# IMU.net
KiCad netlist of a schematic drawn in Altium Designer
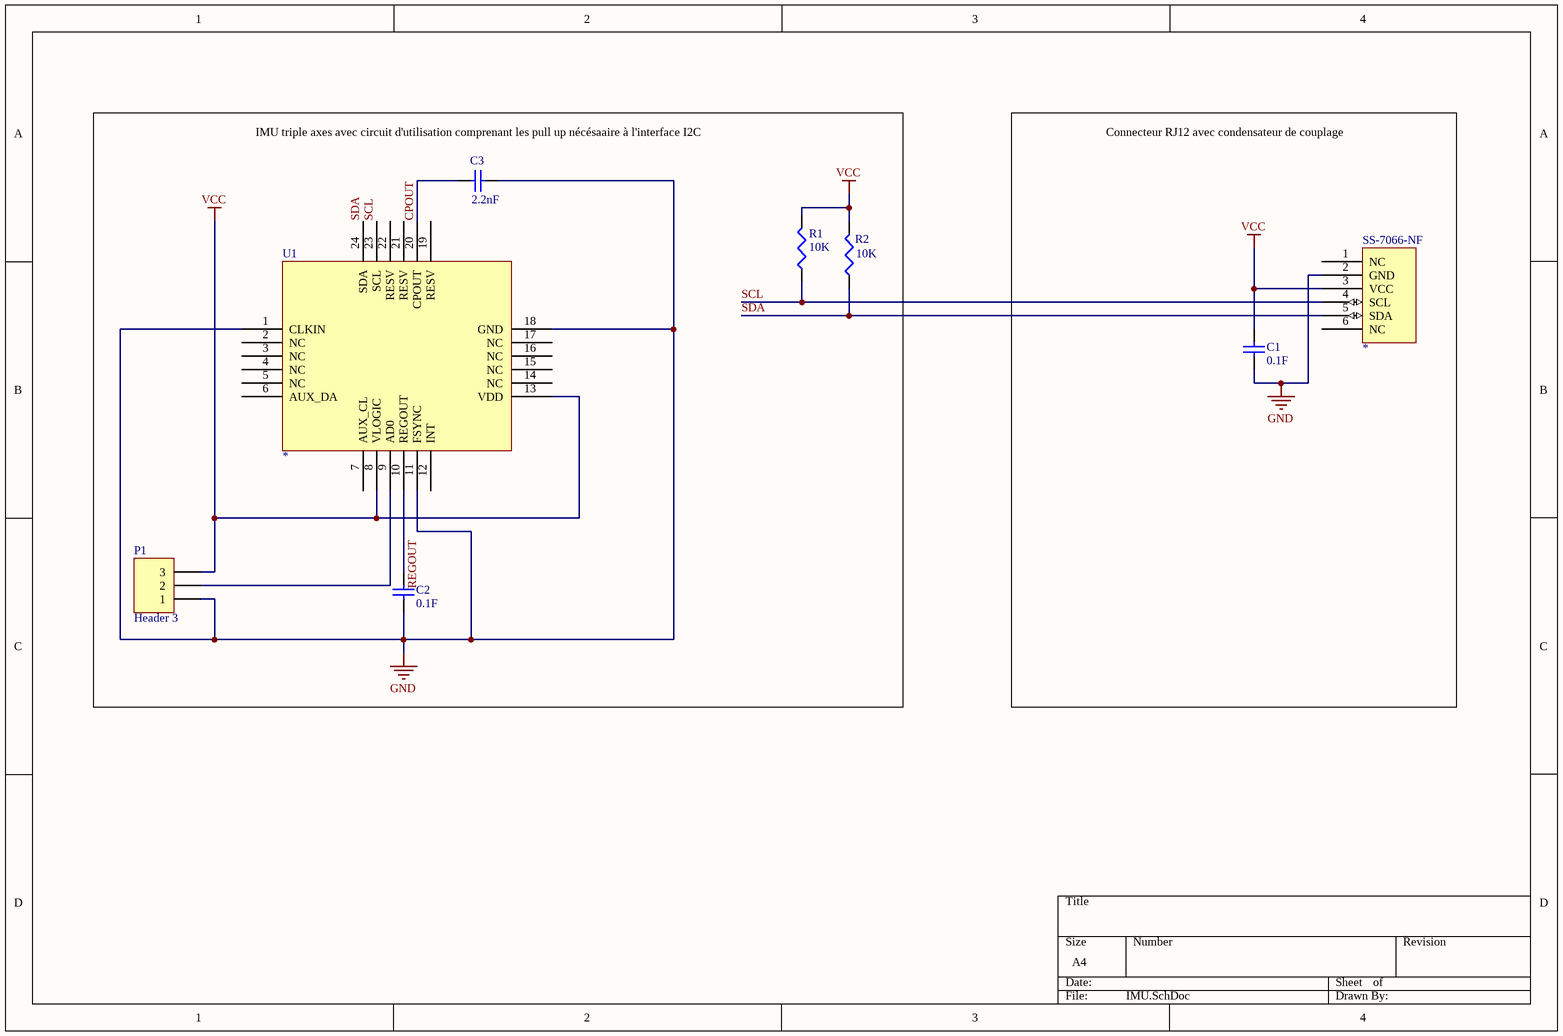
[diagram p0: IMU.SchDoc]

(export (version "E")
  (design (tool "Eeschema 10.0.6"))
  (components
    (comp (ref "C1")
      (value "0.1F")
      (footprint "C0805")
      (description "Capacitor 0.1uF")
      (fields (field (name "Comment") "Cap 0.1uF") (field (name "PUBLISHER") "Altium Limited"))
      (libsource (lib "MOvIT-Detect PCB") (part "Cap 0.1uF"))
    )
    (comp (ref "C2")
      (value "0.1F")
      (footprint "C0805")
      (description "Capacitor 0.1uF")
      (fields (field (name "Comment") "Cap 0.1uF") (field (name "PUBLISHER") "Altium Limited"))
      (libsource (lib "MOvIT-Detect PCB") (part "Cap 0.1uF"))
    )
    (comp (ref "C3")
      (value "2.2nF")
      (footprint "C0805")
      (description "Capacitor 2.2nF")
      (fields (field (name "Comment") "Cap 2.2nF") (field (name "PUBLISHER") "Altium Limited"))
      (libsource (lib "MOvIT-Detect PCB") (part "Cap 2.2nF"))
    )
    (comp (ref "P1")
      (value "Header 3")
      (footprint "HDR1X3")
      (description "Header, 3-Pin")
      (fields (field (name "PUBLISHER") "Altium Limited"))
      (libsource (lib "MOvIT-Detect PCB") (part "Header 3"))
    )
    (comp (ref "R1")
      (value "10K")
      (footprint "6-0805_N")
      (description "Resistor 10K")
      (fields (field (name "Comment") "Res 10K") (field (name "PUBLISHER") "Altium Limited"))
      (libsource (lib "MOvIT-Detect PCB") (part "Res 10K"))
    )
    (comp (ref "R2")
      (value "10K")
      (footprint "6-0805_N")
      (description "Resistor 10K")
      (fields (field (name "Comment") "Res 10K") (field (name "PUBLISHER") "Altium Limited"))
      (libsource (lib "MOvIT-Detect PCB") (part "Res 10K"))
    )
    (comp (ref "SS-7066-NF")
      (value "*")
      (footprint "SS-7066-NF")
      (description "RJ12 Connector")
      (libsource (lib "MOvIT-Detect PCB") (part "SS-7066-NF"))
    )
    (comp (ref "U1")
      (value "*")
      (footprint "MPU6050")
      (description "3 Axis IMU")
      (libsource (lib "MOvIT-Detect PCB") (part "MPU6050"))
    )
  )
  (nets
    (net (code "1") (name "/CPOUT") (class "Default")
      (node (ref "C3") (pin "1") (pinfunction "1_1") (pintype "passive"))
      (node (ref "U1") (pin "20") (pinfunction "CPOUT_20") (pintype "passive"))
    )
    (net (code "2") (name "/REGOUT") (class "Default")
      (node (ref "C2") (pin "2") (pinfunction "2_2") (pintype "passive"))
      (node (ref "U1") (pin "10") (pinfunction "REGOUT_10") (pintype "passive"))
    )
    (net (code "3") (name "/SCL") (class "Default")
      (node (ref "R1") (pin "1") (pinfunction "1_1") (pintype "passive"))
      (node (ref "SS-7066-NF") (pin "4") (pinfunction "SCL_4") (pintype "bidirectional"))
      (node (ref "U1") (pin "23") (pinfunction "SCL_23") (pintype "passive"))
    )
    (net (code "4") (name "/SDA") (class "Default")
      (node (ref "R2") (pin "1") (pinfunction "1_1") (pintype "passive"))
      (node (ref "SS-7066-NF") (pin "5") (pinfunction "SDA_5") (pintype "bidirectional"))
      (node (ref "U1") (pin "24") (pinfunction "SDA_24") (pintype "passive"))
    )
    (net (code "5") (name "GND") (class "Default")
      (node (ref "C1") (pin "1") (pinfunction "1_1") (pintype "passive"))
      (node (ref "C2") (pin "1") (pinfunction "1_1") (pintype "passive"))
      (node (ref "C3") (pin "2") (pinfunction "2_2") (pintype "passive"))
      (node (ref "P1") (pin "1") (pinfunction "1_1") (pintype "passive"))
      (node (ref "SS-7066-NF") (pin "2") (pinfunction "GND_2") (pintype "passive"))
      (node (ref "U1") (pin "1") (pinfunction "CLKIN_1") (pintype "passive"))
      (node (ref "U1") (pin "11") (pinfunction "FSYNC_11") (pintype "passive"))
      (node (ref "U1") (pin "18") (pinfunction "GND_18") (pintype "passive"))
    )
    (net (code "6") (name "Net-(U1-AD0)") (class "Default")
      (node (ref "P1") (pin "2") (pinfunction "2_2") (pintype "passive"))
      (node (ref "U1") (pin "9") (pinfunction "AD0_9") (pintype "passive"))
    )
    (net (code "7") (name "VCC") (class "Default")
      (node (ref "C1") (pin "2") (pinfunction "2_2") (pintype "passive"))
      (node (ref "P1") (pin "3") (pinfunction "3_3") (pintype "passive"))
      (node (ref "R1") (pin "2") (pinfunction "2_2") (pintype "passive"))
      (node (ref "R2") (pin "2") (pinfunction "2_2") (pintype "passive"))
      (node (ref "SS-7066-NF") (pin "3") (pinfunction "VCC_3") (pintype "passive"))
      (node (ref "U1") (pin "13") (pinfunction "VDD_13") (pintype "passive"))
      (node (ref "U1") (pin "8") (pinfunction "VLOGIC_8") (pintype "passive"))
    )
    (net (code "8") (name "unconnected-(SS-7066-NF-NC-Pad1)") (class "Default")
      (node (ref "SS-7066-NF") (pin "1") (pinfunction "NC_1") (pintype "passive"))
    )
    (net (code "9") (name "unconnected-(SS-7066-NF-NC-Pad6)") (class "Default")
      (node (ref "SS-7066-NF") (pin "6") (pinfunction "NC_6") (pintype "passive"))
    )
    (net (code "10") (name "unconnected-(U1-AUX_CL-Pad7)") (class "Default")
      (node (ref "U1") (pin "7") (pinfunction "AUX_CL_7") (pintype "passive"))
    )
    (net (code "11") (name "unconnected-(U1-AUX_DA-Pad6)") (class "Default")
      (node (ref "U1") (pin "6") (pinfunction "AUX_DA_6") (pintype "passive"))
    )
    (net (code "12") (name "unconnected-(U1-INT-Pad12)") (class "Default")
      (node (ref "U1") (pin "12") (pinfunction "INT_12") (pintype "passive"))
    )
    (net (code "13") (name "unconnected-(U1-NC-Pad2)") (class "Default")
      (node (ref "U1") (pin "2") (pinfunction "NC_2") (pintype "passive"))
    )
    (net (code "14") (name "unconnected-(U1-NC-Pad3)") (class "Default")
      (node (ref "U1") (pin "3") (pinfunction "NC_3") (pintype "passive"))
    )
    (net (code "15") (name "unconnected-(U1-NC-Pad4)") (class "Default")
      (node (ref "U1") (pin "4") (pinfunction "NC_4") (pintype "passive"))
    )
    (net (code "16") (name "unconnected-(U1-NC-Pad5)") (class "Default")
      (node (ref "U1") (pin "5") (pinfunction "NC_5") (pintype "passive"))
    )
    (net (code "17") (name "unconnected-(U1-NC-Pad14)") (class "Default")
      (node (ref "U1") (pin "14") (pinfunction "NC_14") (pintype "passive"))
    )
    (net (code "18") (name "unconnected-(U1-NC-Pad15)") (class "Default")
      (node (ref "U1") (pin "15") (pinfunction "NC_15") (pintype "passive"))
    )
    (net (code "19") (name "unconnected-(U1-NC-Pad16)") (class "Default")
      (node (ref "U1") (pin "16") (pinfunction "NC_16") (pintype "passive"))
    )
    (net (code "20") (name "unconnected-(U1-NC-Pad17)") (class "Default")
      (node (ref "U1") (pin "17") (pinfunction "NC_17") (pintype "passive"))
    )
    (net (code "21") (name "unconnected-(U1-RESV-Pad19)") (class "Default")
      (node (ref "U1") (pin "19") (pinfunction "RESV_19") (pintype "passive"))
    )
    (net (code "22") (name "unconnected-(U1-RESV-Pad21)") (class "Default")
      (node (ref "U1") (pin "21") (pinfunction "RESV_21") (pintype "passive"))
    )
    (net (code "23") (name "unconnected-(U1-RESV-Pad22)") (class "Default")
      (node (ref "U1") (pin "22") (pinfunction "RESV_22") (pintype "passive"))
    )
  )
)
